# rapidshark-fuse-mk-1_0.net
KiCad netlist of a schematic drawn in EAGLE
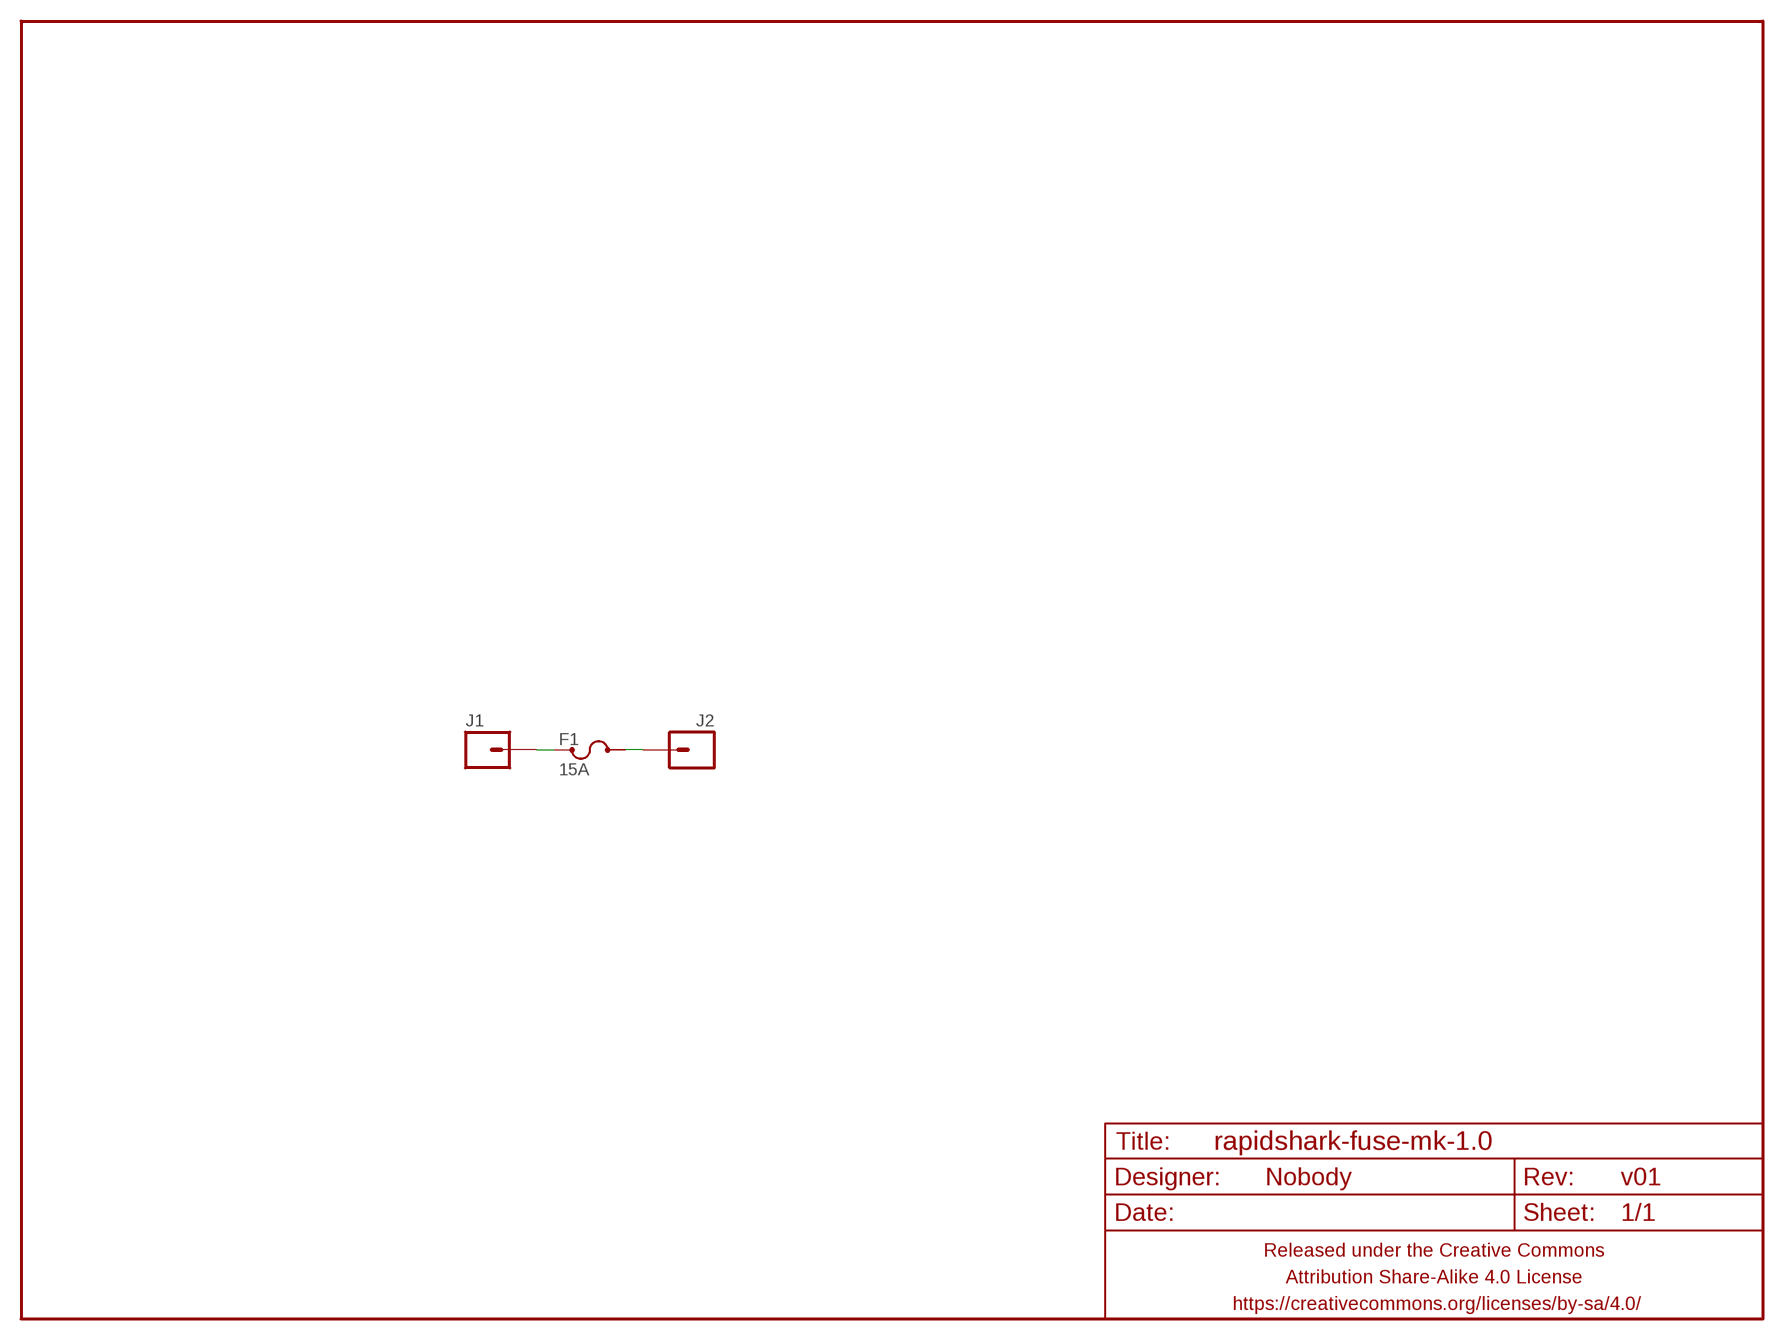
[diagram p0: schematic, sheet 1]

(export (version "E")
  (design (tool "Eeschema 10.0.6"))
  (components
    (comp (ref "F1")
      (value "15A")
      (footprint "eagle-import:KEYSTONE-MINI-AUTO-FUSE-HOLDER")
      (libsource (lib "eagle-import") (part "FUSEMINI-AUTO"))
    )
    (comp (ref "FRAME1")
      (value "FRAME-LETTERNO_PACKAGE")
      (footprint "eagle-import:DUMMY")
      (fields (field (name "DESIGNER") "Nobody"))
      (libsource (lib "eagle-import") (part "FRAME-LETTERNO_PACKAGE"))
    )
    (comp (ref "J1")
      (value "M0112AWG-OFFSET")
      (footprint "eagle-import:1X01-12AWG-OFFSET")
      (libsource (lib "eagle-import") (part "M0112AWG-OFFSET"))
    )
    (comp (ref "J2")
      (value "M0112AWG-OFFSET")
      (footprint "eagle-import:1X01-12AWG-OFFSET")
      (libsource (lib "eagle-import") (part "M0112AWG-OFFSET"))
    )
  )
  (nets
    (net (code "1") (name "Net-(F1-1-PadP1@1)") (class "Default")
      (node (ref "F1") (pin "P1@1") (pinfunction "1_P1@1") (pintype "passive"))
      (node (ref "F1") (pin "P1@2") (pinfunction "1_P1@2") (pintype "passive"))
      (node (ref "J1") (pin "1") (pinfunction "1_1") (pintype "passive"))
    )
    (net (code "2") (name "Net-(F1-2-PadP2@1)") (class "Default")
      (node (ref "F1") (pin "P2@1") (pinfunction "2_P2@1") (pintype "passive"))
      (node (ref "F1") (pin "P2@2") (pinfunction "2_P2@2") (pintype "passive"))
      (node (ref "J2") (pin "1") (pinfunction "1_1") (pintype "passive"))
    )
  )
)
